# esp-lock.net
KiCad netlist of a schematic drawn in EAGLE
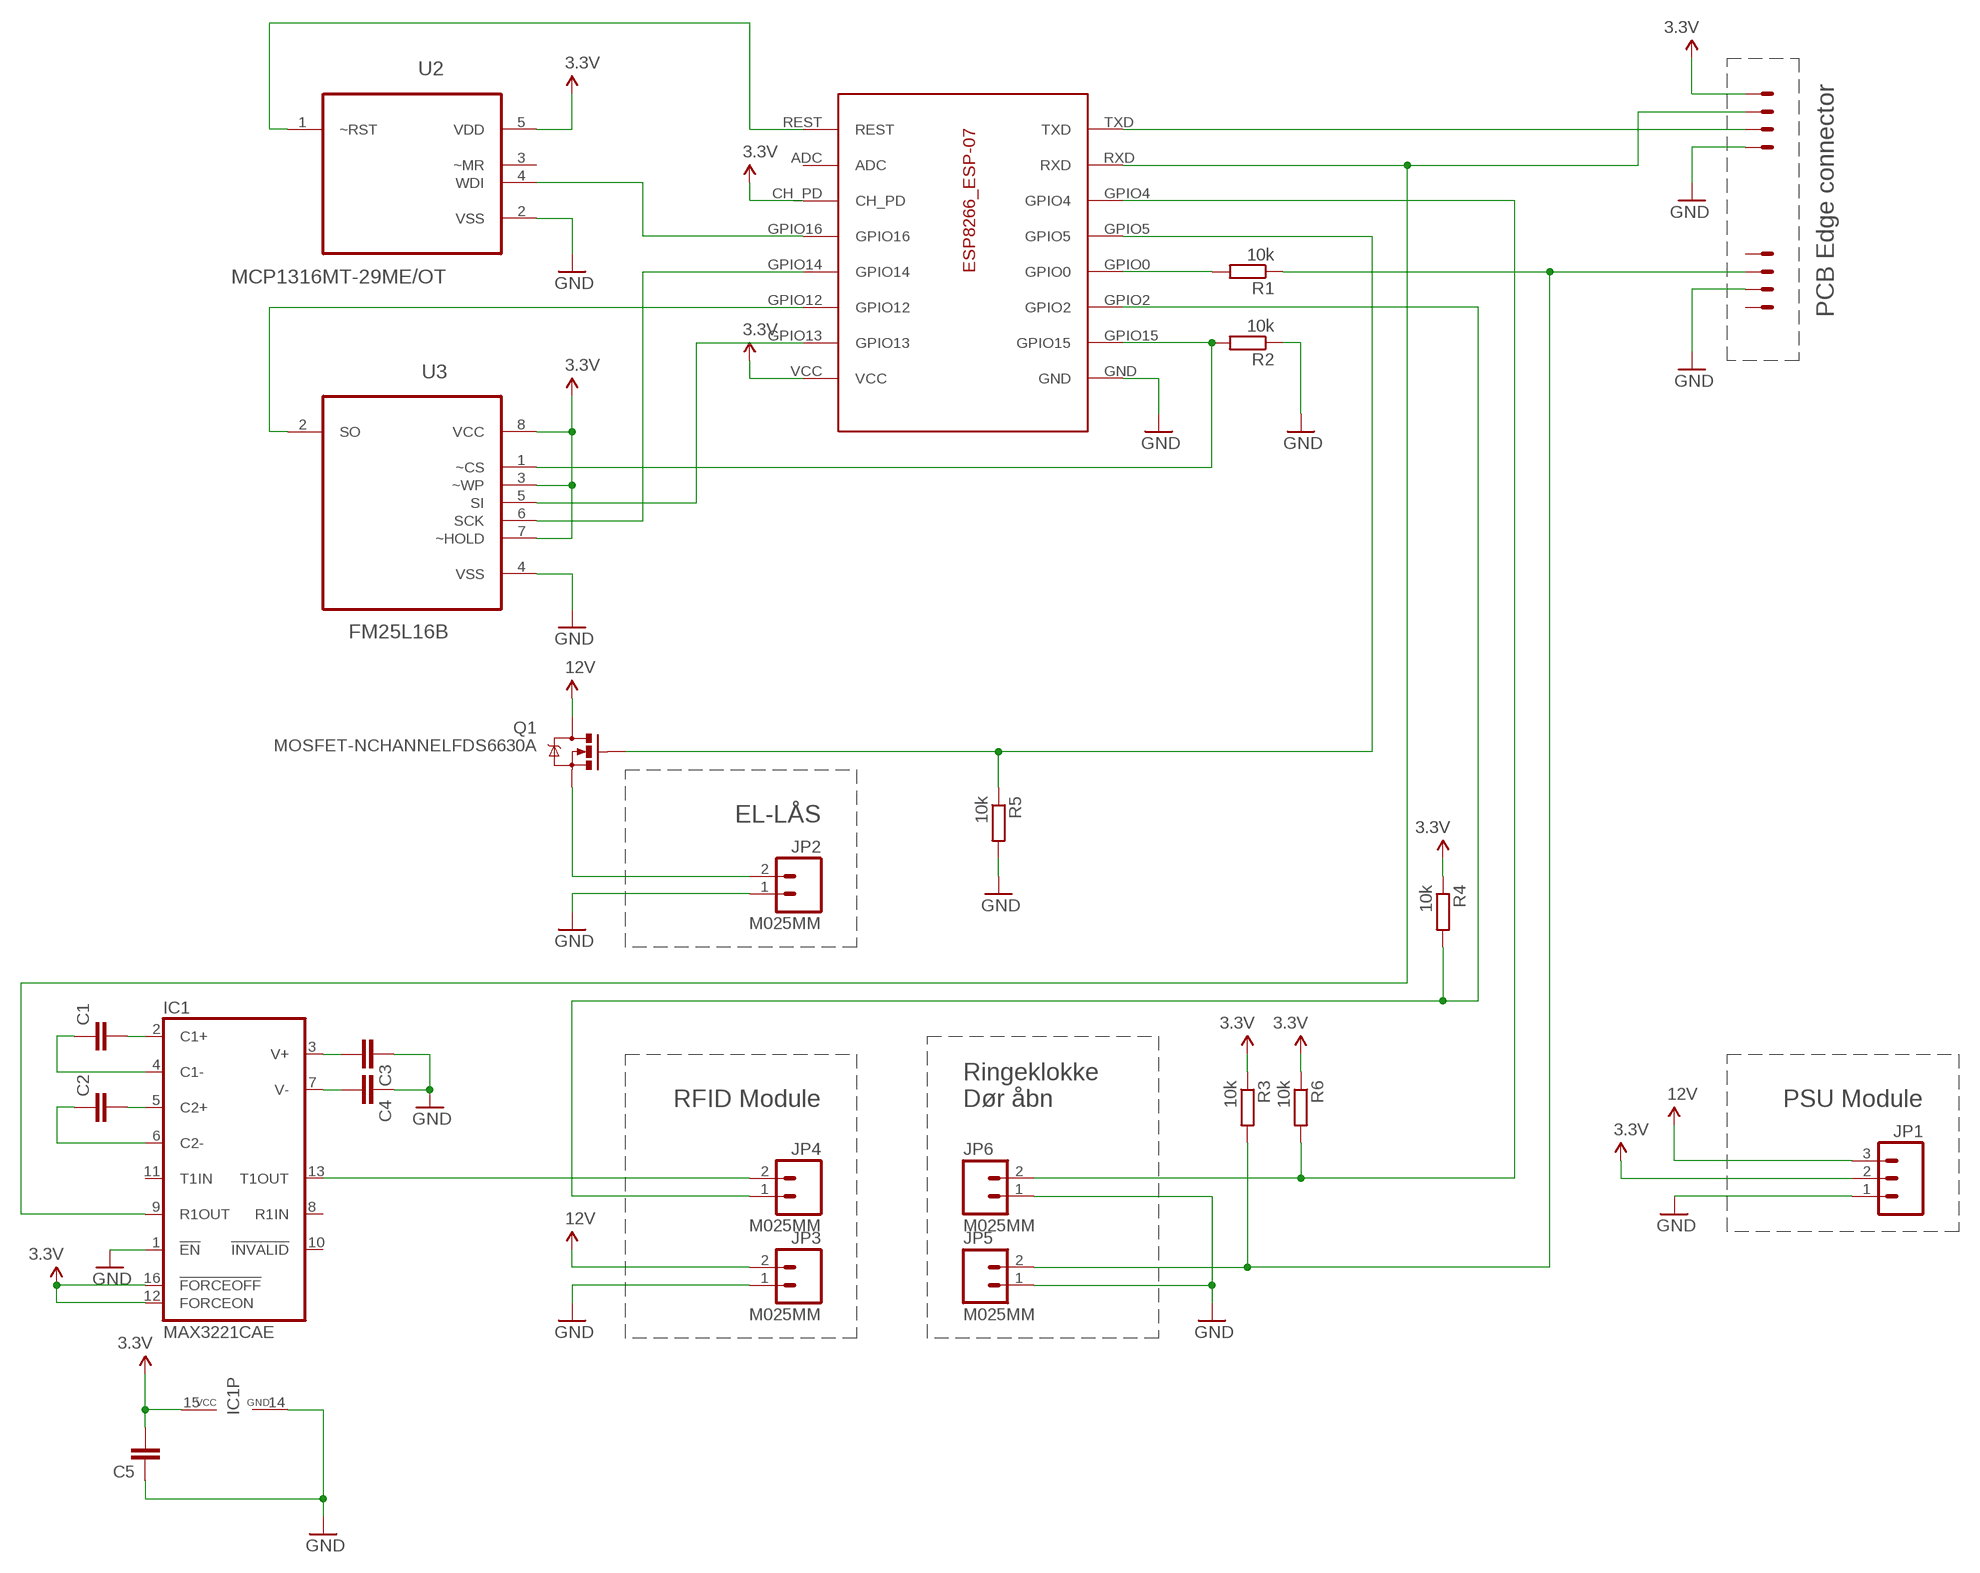
[diagram p0: schematic, sheet 1]

(export (version "E")
  (design (tool "Eeschema 10.0.6"))
  (components
    (comp (ref "C1")
      (value "CAP0402-CAP")
      (footprint "eagle-import:0402-CAP")
      (libsource (lib "eagle-import") (part "CAP0402-CAP"))
    )
    (comp (ref "C2")
      (value "CAP0402-CAP")
      (footprint "eagle-import:0402-CAP")
      (libsource (lib "eagle-import") (part "CAP0402-CAP"))
    )
    (comp (ref "C3")
      (value "CAP0402-CAP")
      (footprint "eagle-import:0402-CAP")
      (libsource (lib "eagle-import") (part "CAP0402-CAP"))
    )
    (comp (ref "C4")
      (value "CAP0402-CAP")
      (footprint "eagle-import:0402-CAP")
      (libsource (lib "eagle-import") (part "CAP0402-CAP"))
    )
    (comp (ref "C5")
      (value "CAP0402-CAP")
      (footprint "eagle-import:0402-CAP")
      (libsource (lib "eagle-import") (part "CAP0402-CAP"))
    )
    (comp (ref "ESP8266_ESP-07")
      (value "ESP8266-07")
      (footprint "eagle-import:ESP-07")
      (libsource (lib "eagle-import") (part "ESP8266-07"))
    )
    (comp (ref "IC1")
      (value "MAX3221CAE")
      (footprint "eagle-import:SSOP16")
      (fields (field (name "MF") "MAXIM") (field (name "MPN") "MAX3221CAE+"))
      (libsource (lib "eagle-import") (part "MAX3221AEC"))
    )
    (comp (ref "JP1")
      (value "M03-SCREW-5MM")
      (footprint "eagle-import:SCREWTERMINAL-5MM-3")
      (libsource (lib "eagle-import") (part "M03-SCREW-5MM"))
    )
    (comp (ref "JP2")
      (value "M025MM")
      (footprint "eagle-import:SCREWTERMINAL-5MM-2")
      (libsource (lib "eagle-import") (part "M025MM"))
    )
    (comp (ref "JP3")
      (value "M025MM")
      (footprint "eagle-import:SCREWTERMINAL-5MM-2")
      (libsource (lib "eagle-import") (part "M025MM"))
    )
    (comp (ref "JP4")
      (value "M025MM")
      (footprint "eagle-import:SCREWTERMINAL-5MM-2")
      (libsource (lib "eagle-import") (part "M025MM"))
    )
    (comp (ref "JP5")
      (value "M025MM")
      (footprint "eagle-import:SCREWTERMINAL-5MM-2")
      (libsource (lib "eagle-import") (part "M025MM"))
    )
    (comp (ref "JP6")
      (value "M025MM")
      (footprint "eagle-import:SCREWTERMINAL-5MM-2")
      (libsource (lib "eagle-import") (part "M025MM"))
    )
    (comp (ref "Q1")
      (value "MOSFET-NCHANNELFDS6630A")
      (footprint "eagle-import:SO08")
      (libsource (lib "eagle-import") (part "MOSFET-NCHANNELFDS6630A"))
    )
    (comp (ref "R1")
      (value "10k")
      (footprint "eagle-import:R0805")
      (libsource (lib "eagle-import") (part "R-EU_R0805"))
    )
    (comp (ref "R2")
      (value "10k")
      (footprint "eagle-import:R0805")
      (libsource (lib "eagle-import") (part "R-EU_R0805"))
    )
    (comp (ref "R3")
      (value "10k")
      (footprint "eagle-import:R0805")
      (libsource (lib "eagle-import") (part "R-EU_R0805"))
    )
    (comp (ref "R4")
      (value "10k")
      (footprint "eagle-import:R0805")
      (libsource (lib "eagle-import") (part "R-EU_R0805"))
    )
    (comp (ref "R5")
      (value "10k")
      (footprint "eagle-import:R0805")
      (libsource (lib "eagle-import") (part "R-EU_R0805"))
    )
    (comp (ref "R6")
      (value "10k")
      (footprint "eagle-import:R0805")
      (libsource (lib "eagle-import") (part "R-EU_R0805"))
    )
    (comp (ref "U$1")
      (value "CON-PCB-SLOT-0.05MINIMAL")
      (footprint "eagle-import:CONN_SLOT_MINIMAL")
      (libsource (lib "eagle-import") (part "CON-PCB-SLOT-0.05MINIMAL"))
    )
    (comp (ref "U2")
      (value "MCP1316MT-29ME/OT")
      (footprint "eagle-import:SOT95P270X145-5N")
      (fields (field (name "MPN") "MCP1316T-29LE/OT"))
      (libsource (lib "eagle-import") (part "MCP1316T-29LE/OT"))
    )
    (comp (ref "U3")
      (value "FM25L16B")
      (footprint "eagle-import:SOIC127P600X175-8N")
      (fields (field (name "MPN") "25AA020A-I/SN"))
      (libsource (lib "eagle-import") (part "25AA020A-I/SN"))
    )
  )
  (nets
    (net (code "1") (name "3.3V") (class "Default")
      (node (ref "C5") (pin "2") (pinfunction "2_2") (pintype "passive"))
      (node (ref "ESP8266_ESP-07") (pin "CH_PD") (pinfunction "CH_PD_CH_PD") (pintype "bidirectional"))
      (node (ref "ESP8266_ESP-07") (pin "VCC") (pinfunction "VCC_VCC") (pintype "bidirectional"))
      (node (ref "IC1") (pin "12") (pinfunction "FORCEON_12") (pintype "input"))
      (node (ref "IC1") (pin "15") (pinfunction "VCC_15") (pintype "power_in"))
      (node (ref "IC1") (pin "16") (pinfunction "~{FORCEOFF}_16") (pintype "input"))
      (node (ref "JP1") (pin "2") (pinfunction "2_2") (pintype "passive"))
      (node (ref "R3") (pin "1") (pinfunction "1_1") (pintype "passive"))
      (node (ref "R4") (pin "1") (pinfunction "1_1") (pintype "passive"))
      (node (ref "R6") (pin "1") (pinfunction "1_1") (pintype "passive"))
      (node (ref "U$1") (pin "4") (pinfunction "S_4") (pintype "passive"))
      (node (ref "U2") (pin "5") (pinfunction "VDD_5") (pintype "power_in"))
      (node (ref "U3") (pin "3") (pinfunction "~{WP}_3") (pintype "input"))
      (node (ref "U3") (pin "7") (pinfunction "~{HOLD}_7") (pintype "input"))
      (node (ref "U3") (pin "8") (pinfunction "VCC_8") (pintype "power_in"))
    )
    (net (code "2") (name "12V") (class "Default")
      (node (ref "JP1") (pin "3") (pinfunction "3_3") (pintype "passive"))
      (node (ref "JP3") (pin "2") (pinfunction "2_2") (pintype "passive"))
      (node (ref "Q1") (pin "5") (pinfunction "D_5") (pintype "passive"))
      (node (ref "Q1") (pin "6") (pinfunction "D_6") (pintype "passive"))
      (node (ref "Q1") (pin "7") (pinfunction "D_7") (pintype "passive"))
      (node (ref "Q1") (pin "8") (pinfunction "D_8") (pintype "passive"))
    )
    (net (code "3") (name "GND") (class "Default")
      (node (ref "C3") (pin "1") (pinfunction "1_1") (pintype "passive"))
      (node (ref "C4") (pin "1") (pinfunction "1_1") (pintype "passive"))
      (node (ref "C5") (pin "1") (pinfunction "1_1") (pintype "passive"))
      (node (ref "ESP8266_ESP-07") (pin "GND") (pinfunction "GND_GND") (pintype "power_in"))
      (node (ref "IC1") (pin "1") (pinfunction "~{EN}_1") (pintype "input"))
      (node (ref "IC1") (pin "14") (pinfunction "GND_14") (pintype "power_in"))
      (node (ref "JP1") (pin "1") (pinfunction "1_1") (pintype "passive"))
      (node (ref "JP2") (pin "1") (pinfunction "1_1") (pintype "passive"))
      (node (ref "JP3") (pin "1") (pinfunction "1_1") (pintype "passive"))
      (node (ref "JP5") (pin "1") (pinfunction "1_1") (pintype "passive"))
      (node (ref "JP6") (pin "1") (pinfunction "1_1") (pintype "passive"))
      (node (ref "R2") (pin "1") (pinfunction "1_1") (pintype "passive"))
      (node (ref "R5") (pin "2") (pinfunction "2_2") (pintype "passive"))
      (node (ref "U$1") (pin "1") (pinfunction "S_1") (pintype "passive"))
      (node (ref "U$1") (pin "7") (pinfunction "S_7") (pintype "passive"))
      (node (ref "U2") (pin "2") (pinfunction "VSS_2") (pintype "power_in"))
      (node (ref "U3") (pin "4") (pinfunction "VSS_4") (pintype "power_in"))
    )
    (net (code "4") (name "Net-(ESP8266_ESP-07-PadGPIO0)") (class "Default")
      (node (ref "ESP8266_ESP-07") (pin "GPIO0") (pinfunction "GPIO0_GPIO0") (pintype "bidirectional"))
      (node (ref "R1") (pin "2") (pinfunction "2_2") (pintype "passive"))
    )
    (net (code "5") (name "Net-(ESP8266_ESP-07-PadGPIO2)") (class "Default")
      (node (ref "ESP8266_ESP-07") (pin "GPIO2") (pinfunction "GPIO2_GPIO2") (pintype "bidirectional"))
      (node (ref "JP4") (pin "1") (pinfunction "1_1") (pintype "passive"))
      (node (ref "R4") (pin "2") (pinfunction "2_2") (pintype "passive"))
    )
    (net (code "6") (name "Net-(ESP8266_ESP-07-PadGPIO4)") (class "Default")
      (node (ref "ESP8266_ESP-07") (pin "GPIO4") (pinfunction "GPIO4_GPIO4") (pintype "bidirectional"))
      (node (ref "JP6") (pin "2") (pinfunction "2_2") (pintype "passive"))
      (node (ref "R6") (pin "2") (pinfunction "2_2") (pintype "passive"))
    )
    (net (code "7") (name "Net-(IC1A-C1+)") (class "Default")
      (node (ref "C1") (pin "2") (pinfunction "2_2") (pintype "passive"))
      (node (ref "IC1") (pin "2") (pinfunction "C1+_2") (pintype "passive"))
    )
    (net (code "8") (name "Net-(IC1A-C1-)") (class "Default")
      (node (ref "C1") (pin "1") (pinfunction "1_1") (pintype "passive"))
      (node (ref "IC1") (pin "4") (pinfunction "C1-_4") (pintype "passive"))
    )
    (net (code "9") (name "Net-(IC1A-C2+)") (class "Default")
      (node (ref "C2") (pin "2") (pinfunction "2_2") (pintype "passive"))
      (node (ref "IC1") (pin "5") (pinfunction "C2+_5") (pintype "passive"))
    )
    (net (code "10") (name "Net-(IC1A-C2-)") (class "Default")
      (node (ref "C2") (pin "1") (pinfunction "1_1") (pintype "passive"))
      (node (ref "IC1") (pin "6") (pinfunction "C2-_6") (pintype "passive"))
    )
    (net (code "11") (name "Net-(IC1A-R1OUT)") (class "Default")
      (node (ref "ESP8266_ESP-07") (pin "RXD") (pinfunction "RXD_RXD") (pintype "bidirectional"))
      (node (ref "IC1") (pin "9") (pinfunction "R1OUT_9") (pintype "output"))
      (node (ref "U$1") (pin "3") (pinfunction "S_3") (pintype "passive"))
    )
    (net (code "12") (name "Net-(IC1A-T1OUT)") (class "Default")
      (node (ref "IC1") (pin "13") (pinfunction "T1OUT_13") (pintype "output"))
      (node (ref "JP4") (pin "2") (pinfunction "2_2") (pintype "passive"))
    )
    (net (code "13") (name "Net-(IC1A-V+)") (class "Default")
      (node (ref "C3") (pin "2") (pinfunction "2_2") (pintype "passive"))
      (node (ref "IC1") (pin "3") (pinfunction "V+_3") (pintype "passive"))
    )
    (net (code "14") (name "Net-(IC1A-V-)") (class "Default")
      (node (ref "C4") (pin "2") (pinfunction "2_2") (pintype "passive"))
      (node (ref "IC1") (pin "7") (pinfunction "V-_7") (pintype "passive"))
    )
    (net (code "15") (name "Net-(JP2-Pad2)") (class "Default")
      (node (ref "JP2") (pin "2") (pinfunction "2_2") (pintype "passive"))
      (node (ref "Q1") (pin "1") (pinfunction "S_1") (pintype "passive"))
      (node (ref "Q1") (pin "2") (pinfunction "S_2") (pintype "passive"))
      (node (ref "Q1") (pin "3") (pinfunction "S_3") (pintype "passive"))
    )
    (net (code "16") (name "Net-(Q1-G)") (class "Default")
      (node (ref "ESP8266_ESP-07") (pin "GPIO5") (pinfunction "GPIO5_GPIO5") (pintype "bidirectional"))
      (node (ref "Q1") (pin "4") (pinfunction "G_4") (pintype "passive"))
      (node (ref "R5") (pin "1") (pinfunction "1_1") (pintype "passive"))
    )
    (net (code "17") (name "Net-(U$1B-S)") (class "Default")
      (node (ref "ESP8266_ESP-07") (pin "TXD") (pinfunction "TXD_TXD") (pintype "bidirectional"))
      (node (ref "U$1") (pin "2") (pinfunction "S_2") (pintype "passive"))
    )
    (net (code "18") (name "Net-(U$1F-S)") (class "Default")
      (node (ref "JP5") (pin "2") (pinfunction "2_2") (pintype "passive"))
      (node (ref "R1") (pin "1") (pinfunction "1_1") (pintype "passive"))
      (node (ref "R3") (pin "2") (pinfunction "2_2") (pintype "passive"))
      (node (ref "U$1") (pin "6") (pinfunction "S_6") (pintype "passive"))
    )
    (net (code "19") (name "Net-(U2-WDI)") (class "Default")
      (node (ref "ESP8266_ESP-07") (pin "GPIO16") (pinfunction "GPIO16_GPIO16") (pintype "bidirectional"))
      (node (ref "U2") (pin "4") (pinfunction "WDI_4") (pintype "input"))
    )
    (net (code "20") (name "Net-(U2-~{RST})") (class "Default")
      (node (ref "ESP8266_ESP-07") (pin "REST") (pinfunction "REST_REST") (pintype "bidirectional"))
      (node (ref "U2") (pin "1") (pinfunction "~{RST}_1") (pintype "output"))
    )
    (net (code "21") (name "Net-(U3-SCK)") (class "Default")
      (node (ref "ESP8266_ESP-07") (pin "GPIO14") (pinfunction "GPIO14_GPIO14") (pintype "bidirectional"))
      (node (ref "U3") (pin "6") (pinfunction "SCK_6") (pintype "input"))
    )
    (net (code "22") (name "Net-(U3-SI)") (class "Default")
      (node (ref "ESP8266_ESP-07") (pin "GPIO13") (pinfunction "GPIO13_GPIO13") (pintype "bidirectional"))
      (node (ref "U3") (pin "5") (pinfunction "SI_5") (pintype "input"))
    )
    (net (code "23") (name "Net-(U3-SO)") (class "Default")
      (node (ref "ESP8266_ESP-07") (pin "GPIO12") (pinfunction "GPIO12_GPIO12") (pintype "bidirectional"))
      (node (ref "U3") (pin "2") (pinfunction "SO_2") (pintype "output"))
    )
    (net (code "24") (name "Net-(U3-~{CS})") (class "Default")
      (node (ref "ESP8266_ESP-07") (pin "GPIO15") (pinfunction "GPIO15_GPIO15") (pintype "bidirectional"))
      (node (ref "R2") (pin "2") (pinfunction "2_2") (pintype "passive"))
      (node (ref "U3") (pin "1") (pinfunction "~{CS}_1") (pintype "input"))
    )
    (net (code "25") (name "unconnected-(ESP8266_ESP-07-PadADC)") (class "Default")
      (node (ref "ESP8266_ESP-07") (pin "ADC") (pinfunction "ADC_ADC") (pintype "bidirectional"))
    )
    (net (code "26") (name "unconnected-(IC1A-R1IN-Pad8)") (class "Default")
      (node (ref "IC1") (pin "8") (pinfunction "R1IN_8") (pintype "input"))
    )
    (net (code "27") (name "unconnected-(IC1A-T1IN-Pad11)") (class "Default")
      (node (ref "IC1") (pin "11") (pinfunction "T1IN_11") (pintype "input"))
    )
    (net (code "28") (name "unconnected-(IC1A-~{INVALID}-Pad10)") (class "Default")
      (node (ref "IC1") (pin "10") (pinfunction "~{INVALID}_10") (pintype "input"))
    )
    (net (code "29") (name "unconnected-(U$1E-S-Pad5)") (class "Default")
      (node (ref "U$1") (pin "5") (pinfunction "S_5") (pintype "passive"))
    )
    (net (code "30") (name "unconnected-(U$1H-S-Pad8)") (class "Default")
      (node (ref "U$1") (pin "8") (pinfunction "S_8") (pintype "passive"))
    )
    (net (code "31") (name "unconnected-(U2-~{MR}-Pad3)") (class "Default")
      (node (ref "U2") (pin "3") (pinfunction "~{MR}_3") (pintype "input"))
    )
  )
)
